# ADC_Shield.net
KiCad netlist of a schematic drawn in Altium Designer
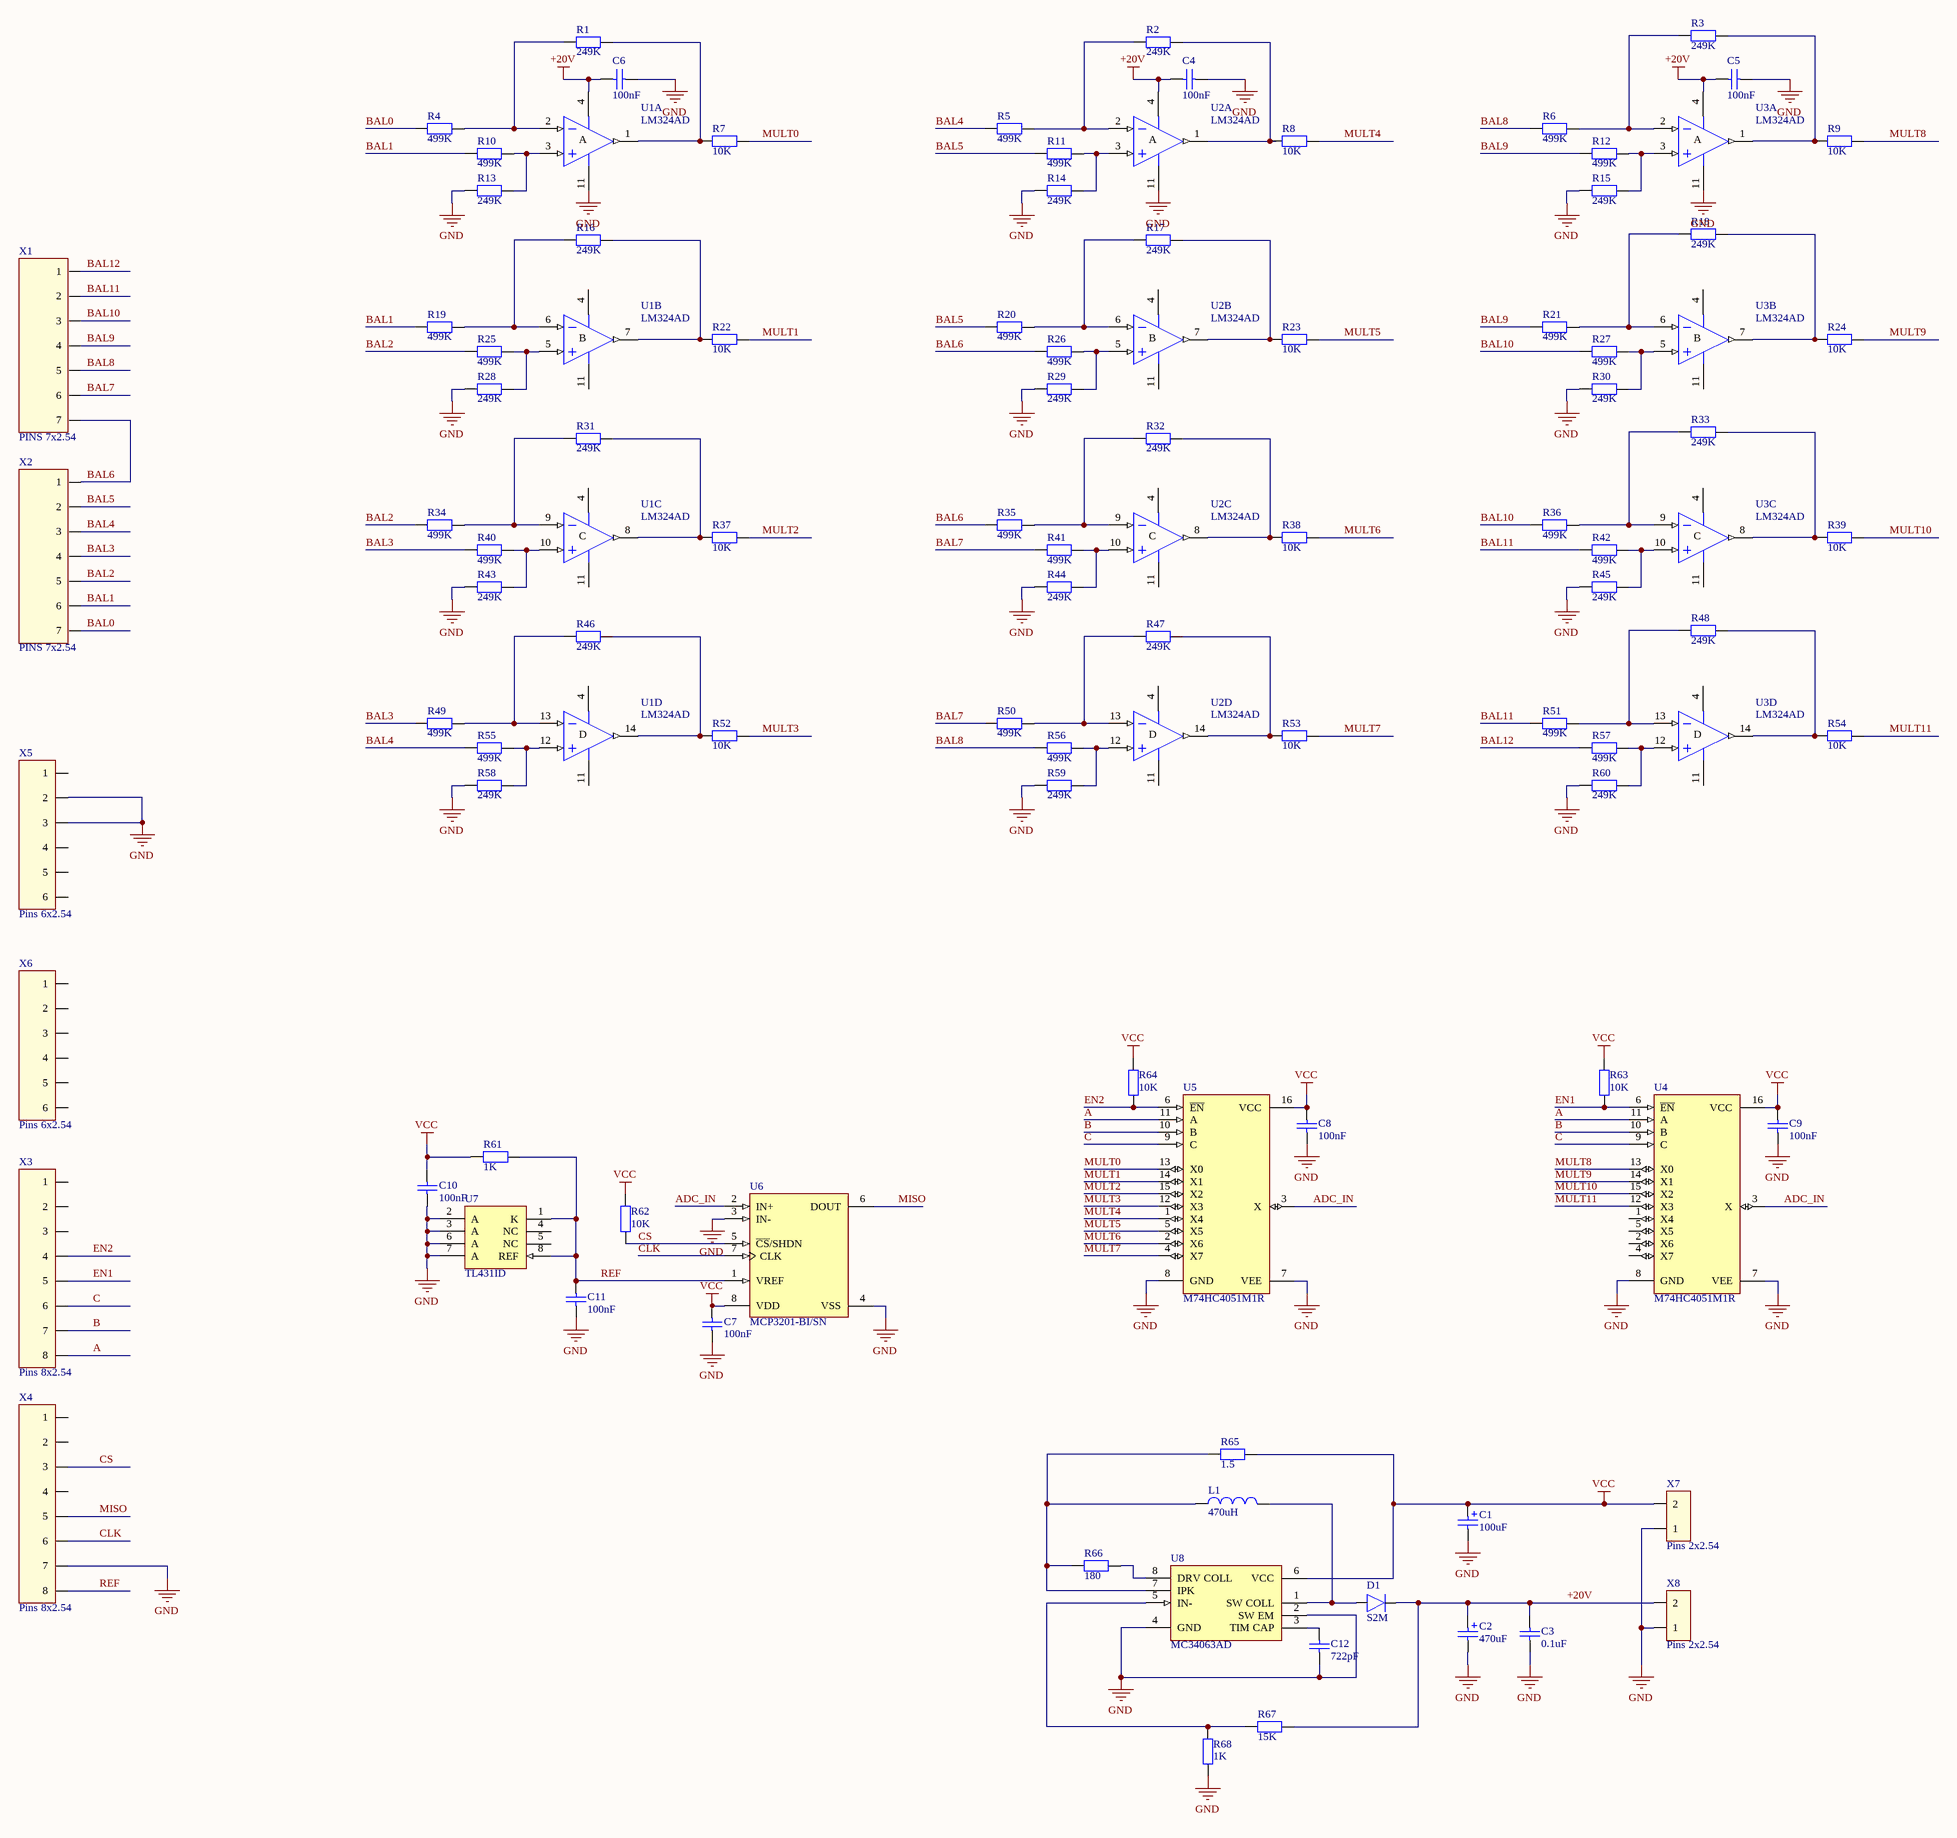
[diagram p0: ADC_Shield.SchDoc]

(export (version "E")
  (design (tool "Eeschema 10.0.6"))
  (components
    (comp (ref "C1")
      (value "100uF")
      (footprint "A_H_pcb_lib:CAP_EL_SMD_6.3mm")
      (libsource (lib "A_H_sch_lib") (part "Cond_polar"))
    )
    (comp (ref "C2")
      (value "470uF")
      (footprint "A_H_pcb_lib:Cap_El_SMD_10mm")
      (libsource (lib "A_H_sch_lib") (part "Cond_polar"))
    )
    (comp (ref "C3")
      (value "0.1uF")
      (footprint "A_H_pcb_lib:C0805")
      (libsource (lib "A_H_sch_lib") (part "Condensator"))
    )
    (comp (ref "C4")
      (value "100nF")
      (footprint "A_H_pcb_lib:C0805")
      (libsource (lib "A_H_sch_lib") (part "Condensator"))
    )
    (comp (ref "C5")
      (value "100nF")
      (footprint "A_H_pcb_lib:C0805")
      (libsource (lib "A_H_sch_lib") (part "Condensator"))
    )
    (comp (ref "C6")
      (value "100nF")
      (footprint "A_H_pcb_lib:C0805")
      (libsource (lib "A_H_sch_lib") (part "Condensator"))
    )
    (comp (ref "C7")
      (value "100nF")
      (footprint "A_H_pcb_lib:C0805")
      (libsource (lib "A_H_sch_lib") (part "Condensator"))
    )
    (comp (ref "C8")
      (value "100nF")
      (footprint "A_H_pcb_lib:C0805")
      (libsource (lib "A_H_sch_lib") (part "Condensator"))
    )
    (comp (ref "C9")
      (value "100nF")
      (footprint "A_H_pcb_lib:C0805")
      (libsource (lib "A_H_sch_lib") (part "Condensator"))
    )
    (comp (ref "C10")
      (value "100nF")
      (footprint "A_H_pcb_lib:C0805")
      (libsource (lib "A_H_sch_lib") (part "Condensator"))
    )
    (comp (ref "C11")
      (value "100nF")
      (footprint "A_H_pcb_lib:C0805")
      (libsource (lib "A_H_sch_lib") (part "Condensator"))
    )
    (comp (ref "C12")
      (value "722pF")
      (footprint "A_H_pcb_lib:C0805")
      (libsource (lib "A_H_sch_lib") (part "Condensator"))
    )
    (comp (ref "D1")
      (value "S2M")
      (footprint "A_H_pcb_lib:SMB_DIODE")
      (libsource (lib "A_H_sch_lib") (part "Diod"))
    )
    (comp (ref "L1")
      (value "470uH")
      (footprint "A_H_pcb_lib:L1812")
      (libsource (lib "A_H_sch_lib") (part "Inductance"))
    )
    (comp (ref "R1") (value "249K") (footprint "R0805") (libsource (lib "A_H_sch_lib") (part "Resistor")))
    (comp (ref "R2") (value "249K") (footprint "R0805") (libsource (lib "A_H_sch_lib") (part "Resistor")))
    (comp (ref "R3") (value "249K") (footprint "R0805") (libsource (lib "A_H_sch_lib") (part "Resistor")))
    (comp (ref "R4") (value "499K") (footprint "R0805") (libsource (lib "A_H_sch_lib") (part "Resistor")))
    (comp (ref "R5") (value "499K") (footprint "R0805") (libsource (lib "A_H_sch_lib") (part "Resistor")))
    (comp (ref "R6") (value "499K") (footprint "R0805") (libsource (lib "A_H_sch_lib") (part "Resistor")))
    (comp (ref "R7") (value "10K") (footprint "R0805") (libsource (lib "A_H_sch_lib") (part "Resistor")))
    (comp (ref "R8") (value "10K") (footprint "R0805") (libsource (lib "A_H_sch_lib") (part "Resistor")))
    (comp (ref "R9") (value "10K") (footprint "R0805") (libsource (lib "A_H_sch_lib") (part "Resistor")))
    (comp (ref "R10") (value "499K") (footprint "R0805") (libsource (lib "A_H_sch_lib") (part "Resistor")))
    (comp (ref "R11") (value "499K") (footprint "R0805") (libsource (lib "A_H_sch_lib") (part "Resistor")))
    (comp (ref "R12") (value "499K") (footprint "R0805") (libsource (lib "A_H_sch_lib") (part "Resistor")))
    (comp (ref "R13") (value "249K") (footprint "R0805") (libsource (lib "A_H_sch_lib") (part "Resistor")))
    (comp (ref "R14") (value "249K") (footprint "R0805") (libsource (lib "A_H_sch_lib") (part "Resistor")))
    (comp (ref "R15") (value "249K") (footprint "R0805") (libsource (lib "A_H_sch_lib") (part "Resistor")))
    (comp (ref "R16") (value "249K") (footprint "R0805") (libsource (lib "A_H_sch_lib") (part "Resistor")))
    (comp (ref "R17") (value "249K") (footprint "R0805") (libsource (lib "A_H_sch_lib") (part "Resistor")))
    (comp (ref "R18") (value "249K") (footprint "R0805") (libsource (lib "A_H_sch_lib") (part "Resistor")))
    (comp (ref "R19") (value "499K") (footprint "R0805") (libsource (lib "A_H_sch_lib") (part "Resistor")))
    (comp (ref "R20") (value "499K") (footprint "R0805") (libsource (lib "A_H_sch_lib") (part "Resistor")))
    (comp (ref "R21") (value "499K") (footprint "R0805") (libsource (lib "A_H_sch_lib") (part "Resistor")))
    (comp (ref "R22") (value "10K") (footprint "R0805") (libsource (lib "A_H_sch_lib") (part "Resistor")))
    (comp (ref "R23") (value "10K") (footprint "R0805") (libsource (lib "A_H_sch_lib") (part "Resistor")))
    (comp (ref "R24") (value "10K") (footprint "R0805") (libsource (lib "A_H_sch_lib") (part "Resistor")))
    (comp (ref "R25") (value "499K") (footprint "R0805") (libsource (lib "A_H_sch_lib") (part "Resistor")))
    (comp (ref "R26") (value "499K") (footprint "R0805") (libsource (lib "A_H_sch_lib") (part "Resistor")))
    (comp (ref "R27") (value "499K") (footprint "R0805") (libsource (lib "A_H_sch_lib") (part "Resistor")))
    (comp (ref "R28") (value "249K") (footprint "R0805") (libsource (lib "A_H_sch_lib") (part "Resistor")))
    (comp (ref "R29") (value "249K") (footprint "R0805") (libsource (lib "A_H_sch_lib") (part "Resistor")))
    (comp (ref "R30") (value "249K") (footprint "R0805") (libsource (lib "A_H_sch_lib") (part "Resistor")))
    (comp (ref "R31") (value "249K") (footprint "R0805") (libsource (lib "A_H_sch_lib") (part "Resistor")))
    (comp (ref "R32") (value "249K") (footprint "R0805") (libsource (lib "A_H_sch_lib") (part "Resistor")))
    (comp (ref "R33") (value "249K") (footprint "R0805") (libsource (lib "A_H_sch_lib") (part "Resistor")))
    (comp (ref "R34") (value "499K") (footprint "R0805") (libsource (lib "A_H_sch_lib") (part "Resistor")))
    (comp (ref "R35") (value "499K") (footprint "R0805") (libsource (lib "A_H_sch_lib") (part "Resistor")))
    (comp (ref "R36") (value "499K") (footprint "R0805") (libsource (lib "A_H_sch_lib") (part "Resistor")))
    (comp (ref "R37") (value "10K") (footprint "R0805") (libsource (lib "A_H_sch_lib") (part "Resistor")))
    (comp (ref "R38") (value "10K") (footprint "R0805") (libsource (lib "A_H_sch_lib") (part "Resistor")))
    (comp (ref "R39") (value "10K") (footprint "R0805") (libsource (lib "A_H_sch_lib") (part "Resistor")))
    (comp (ref "R40") (value "499K") (footprint "R0805") (libsource (lib "A_H_sch_lib") (part "Resistor")))
    (comp (ref "R41") (value "499K") (footprint "R0805") (libsource (lib "A_H_sch_lib") (part "Resistor")))
    (comp (ref "R42") (value "499K") (footprint "R0805") (libsource (lib "A_H_sch_lib") (part "Resistor")))
    (comp (ref "R43") (value "249K") (footprint "R0805") (libsource (lib "A_H_sch_lib") (part "Resistor")))
    (comp (ref "R44") (value "249K") (footprint "R0805") (libsource (lib "A_H_sch_lib") (part "Resistor")))
    (comp (ref "R45") (value "249K") (footprint "R0805") (libsource (lib "A_H_sch_lib") (part "Resistor")))
    (comp (ref "R46") (value "249K") (footprint "R0805") (libsource (lib "A_H_sch_lib") (part "Resistor")))
    (comp (ref "R47") (value "249K") (footprint "R0805") (libsource (lib "A_H_sch_lib") (part "Resistor")))
    (comp (ref "R48") (value "249K") (footprint "R0805") (libsource (lib "A_H_sch_lib") (part "Resistor")))
    (comp (ref "R49") (value "499K") (footprint "R0805") (libsource (lib "A_H_sch_lib") (part "Resistor")))
    (comp (ref "R50") (value "499K") (footprint "R0805") (libsource (lib "A_H_sch_lib") (part "Resistor")))
    (comp (ref "R51") (value "499K") (footprint "R0805") (libsource (lib "A_H_sch_lib") (part "Resistor")))
    (comp (ref "R52") (value "10K") (footprint "R0805") (libsource (lib "A_H_sch_lib") (part "Resistor")))
    (comp (ref "R53") (value "10K") (footprint "R0805") (libsource (lib "A_H_sch_lib") (part "Resistor")))
    (comp (ref "R54") (value "10K") (footprint "R0805") (libsource (lib "A_H_sch_lib") (part "Resistor")))
    (comp (ref "R55") (value "499K") (footprint "R0805") (libsource (lib "A_H_sch_lib") (part "Resistor")))
    (comp (ref "R56") (value "499K") (footprint "R0805") (libsource (lib "A_H_sch_lib") (part "Resistor")))
    (comp (ref "R57") (value "499K") (footprint "R0805") (libsource (lib "A_H_sch_lib") (part "Resistor")))
    (comp (ref "R58") (value "249K") (footprint "R0805") (libsource (lib "A_H_sch_lib") (part "Resistor")))
    (comp (ref "R59") (value "249K") (footprint "R0805") (libsource (lib "A_H_sch_lib") (part "Resistor")))
    (comp (ref "R60") (value "249K") (footprint "R0805") (libsource (lib "A_H_sch_lib") (part "Resistor")))
    (comp (ref "R61") (value "1K") (footprint "R0805") (libsource (lib "A_H_sch_lib") (part "Resistor")))
    (comp (ref "R62") (value "10K") (footprint "R0805") (libsource (lib "") (part "Resistor_1")))
    (comp (ref "R63") (value "10K") (footprint "R0805") (libsource (lib "") (part "Resistor_1")))
    (comp (ref "R64") (value "10K") (footprint "R0805") (libsource (lib "") (part "Resistor_1")))
    (comp (ref "R65") (value "1.5") (footprint "R0805") (libsource (lib "") (part "Resistor_2")))
    (comp (ref "R66") (value "180") (footprint "R0805") (libsource (lib "") (part "Resistor_2")))
    (comp (ref "R67") (value "15K") (footprint "R0805") (libsource (lib "A_H_sch_lib") (part "Resistor")))
    (comp (ref "R68") (value "1K") (footprint "R0805") (libsource (lib "") (part "Resistor_1")))
    (comp (ref "U1")
      (value "LM324AD")
      (footprint "SO14_N")
      (description "Low-Power Quad Operational Amplifier")
      (fields (field (name "PUBLISHER") "Altium Limited"))
      (libsource (lib "ST Operational Amplifier") (part "LM324AD"))
    )
    (comp (ref "U2")
      (value "LM324AD")
      (footprint "SO14_N")
      (description "Low-Power Quad Operational Amplifier")
      (fields (field (name "PUBLISHER") "Altium Limited"))
      (libsource (lib "ST Operational Amplifier") (part "LM324AD"))
    )
    (comp (ref "U3")
      (value "LM324AD")
      (footprint "SO14_N")
      (description "Low-Power Quad Operational Amplifier")
      (fields (field (name "PUBLISHER") "Altium Limited"))
      (libsource (lib "ST Operational Amplifier") (part "LM324AD"))
    )
    (comp (ref "U4")
      (value "M74HC4051M1R")
      (footprint "SO16_N")
      (description "Analog Multiplexer/Demultiplexer Single 8-Channel")
      (fields (field (name "PUBLISHER") "Altium Limited"))
      (libsource (lib "ST Logic Multiplexer") (part "M74HC4051M1R"))
    )
    (comp (ref "U5")
      (value "M74HC4051M1R")
      (footprint "SO16_N")
      (description "Analog Multiplexer/Demultiplexer Single 8-Channel")
      (fields (field (name "PUBLISHER") "Altium Limited"))
      (libsource (lib "ST Logic Multiplexer") (part "M74HC4051M1R"))
    )
    (comp (ref "U6")
      (value "MCP3201-BI/SN")
      (footprint "SO8")
      (libsource (lib "A_H_sch_lib") (part "MCP3201-BI/SN"))
    )
    (comp (ref "U7")
      (value "TL431ID")
      (footprint "SO8_N")
      (description "Programmable Voltage Reference")
      (fields (field (name "PUBLISHER") "Altium Limited"))
      (libsource (lib "ST Power Mgt Voltage Reference") (part "TL431ID"))
    )
    (comp (ref "U8")
      (value "MC34063AD")
      (footprint "751-05_N")
      (description "DC-to-DC Converter Control Circuit")
      (fields (field (name "PUBLISHER") "Altium Limited"))
      (libsource (lib "ON Semi Power Mgt DC-DC Converter") (part "MC34063AD"))
    )
    (comp (ref "X1")
      (value "PINS 7x2.54")
      (footprint "A_H_pcb_lib:PINS 7X2.54R angle")
      (libsource (lib "A_H_sch_lib") (part "PINS 7x2.54"))
    )
    (comp (ref "X2")
      (value "PINS 7x2.54")
      (footprint "A_H_pcb_lib:PINS 7X2.54R angle")
      (libsource (lib "A_H_sch_lib") (part "PINS 7x2.54"))
    )
    (comp (ref "X3")
      (value "Pins 8x2.54")
      (footprint "Pins 8x2.54")
      (libsource (lib "A_H_sch_lib") (part "Pins 8x2.54"))
    )
    (comp (ref "X4")
      (value "Pins 8x2.54")
      (footprint "Pins 8x2.54")
      (libsource (lib "A_H_sch_lib") (part "Pins 8x2.54"))
    )
    (comp (ref "X5")
      (value "Pins 6x2.54")
      (footprint "Pins 6x2.54")
      (libsource (lib "A_H_sch_lib") (part "Pins 6x2.54"))
    )
    (comp (ref "X6")
      (value "Pins 6x2.54")
      (footprint "Pins 6x2.54")
      (libsource (lib "A_H_sch_lib") (part "Pins 6x2.54"))
    )
    (comp (ref "X7")
      (value "Pins 2x2.54")
      (footprint "Pins 2x2.54")
      (libsource (lib "A_H_sch_lib") (part "Pins 2x2.54"))
    )
    (comp (ref "X8")
      (value "Pins 2x2.54")
      (footprint "Pins 2x2.54")
      (libsource (lib "A_H_sch_lib") (part "Pins 2x2.54"))
    )
  )
  (nets
    (net (code "1") (name "+20V") (class "Default")
      (node (ref "C2") (pin "1") (pinfunction "1_1") (pintype "passive"))
      (node (ref "C3") (pin "2") (pinfunction "2_2") (pintype "passive"))
      (node (ref "C4") (pin "1") (pinfunction "1_1") (pintype "passive"))
      (node (ref "C5") (pin "1") (pinfunction "1_1") (pintype "passive"))
      (node (ref "C6") (pin "1") (pinfunction "1_1") (pintype "passive"))
      (node (ref "D1") (pin "2") (pinfunction "2_2") (pintype "passive"))
      (node (ref "R67") (pin "2") (pinfunction "2_2") (pintype "passive"))
      (node (ref "U1") (pin "4") (pinfunction "V+_4") (pintype "power_in"))
      (node (ref "U2") (pin "4") (pinfunction "V+_4") (pintype "power_in"))
      (node (ref "U3") (pin "4") (pinfunction "V+_4") (pintype "power_in"))
      (node (ref "X8") (pin "2") (pinfunction "2_2") (pintype "passive"))
    )
    (net (code "2") (name "/A") (class "Default")
      (node (ref "U4") (pin "11") (pinfunction "A_11") (pintype "input"))
      (node (ref "U5") (pin "11") (pinfunction "A_11") (pintype "input"))
      (node (ref "X3") (pin "8") (pinfunction "8_8") (pintype "passive"))
    )
    (net (code "3") (name "/ADC_IN") (class "Default")
      (node (ref "U4") (pin "3") (pinfunction "X_3") (pintype "bidirectional"))
      (node (ref "U5") (pin "3") (pinfunction "X_3") (pintype "bidirectional"))
      (node (ref "U6") (pin "2") (pinfunction "IN+_2") (pintype "input"))
    )
    (net (code "4") (name "/B") (class "Default")
      (node (ref "U4") (pin "10") (pinfunction "B_10") (pintype "input"))
      (node (ref "U5") (pin "10") (pinfunction "B_10") (pintype "input"))
      (node (ref "X3") (pin "7") (pinfunction "7_7") (pintype "passive"))
    )
    (net (code "5") (name "/BAL0") (class "Default")
      (node (ref "R4") (pin "1") (pinfunction "1_1") (pintype "passive"))
      (node (ref "X2") (pin "7") (pinfunction "7_7") (pintype "passive"))
    )
    (net (code "6") (name "/BAL1") (class "Default")
      (node (ref "R10") (pin "1") (pinfunction "1_1") (pintype "passive"))
      (node (ref "R19") (pin "1") (pinfunction "1_1") (pintype "passive"))
      (node (ref "X2") (pin "6") (pinfunction "6_6") (pintype "passive"))
    )
    (net (code "7") (name "/BAL2") (class "Default")
      (node (ref "R25") (pin "1") (pinfunction "1_1") (pintype "passive"))
      (node (ref "R34") (pin "1") (pinfunction "1_1") (pintype "passive"))
      (node (ref "X2") (pin "5") (pinfunction "5_5") (pintype "passive"))
    )
    (net (code "8") (name "/BAL3") (class "Default")
      (node (ref "R40") (pin "1") (pinfunction "1_1") (pintype "passive"))
      (node (ref "R49") (pin "1") (pinfunction "1_1") (pintype "passive"))
      (node (ref "X2") (pin "4") (pinfunction "4_4") (pintype "passive"))
    )
    (net (code "9") (name "/BAL4") (class "Default")
      (node (ref "R5") (pin "1") (pinfunction "1_1") (pintype "passive"))
      (node (ref "R55") (pin "1") (pinfunction "1_1") (pintype "passive"))
      (node (ref "X2") (pin "3") (pinfunction "3_3") (pintype "passive"))
    )
    (net (code "10") (name "/BAL5") (class "Default")
      (node (ref "R11") (pin "1") (pinfunction "1_1") (pintype "passive"))
      (node (ref "R20") (pin "1") (pinfunction "1_1") (pintype "passive"))
      (node (ref "X2") (pin "2") (pinfunction "2_2") (pintype "passive"))
    )
    (net (code "11") (name "/BAL6") (class "Default")
      (node (ref "R26") (pin "1") (pinfunction "1_1") (pintype "passive"))
      (node (ref "R35") (pin "1") (pinfunction "1_1") (pintype "passive"))
      (node (ref "X1") (pin "7") (pinfunction "7_7") (pintype "passive"))
      (node (ref "X2") (pin "1") (pinfunction "1_1") (pintype "passive"))
    )
    (net (code "12") (name "/BAL7") (class "Default")
      (node (ref "R41") (pin "1") (pinfunction "1_1") (pintype "passive"))
      (node (ref "R50") (pin "1") (pinfunction "1_1") (pintype "passive"))
      (node (ref "X1") (pin "6") (pinfunction "6_6") (pintype "passive"))
    )
    (net (code "13") (name "/BAL8") (class "Default")
      (node (ref "R56") (pin "1") (pinfunction "1_1") (pintype "passive"))
      (node (ref "R6") (pin "1") (pinfunction "1_1") (pintype "passive"))
      (node (ref "X1") (pin "5") (pinfunction "5_5") (pintype "passive"))
    )
    (net (code "14") (name "/BAL9") (class "Default")
      (node (ref "R12") (pin "1") (pinfunction "1_1") (pintype "passive"))
      (node (ref "R21") (pin "1") (pinfunction "1_1") (pintype "passive"))
      (node (ref "X1") (pin "4") (pinfunction "4_4") (pintype "passive"))
    )
    (net (code "15") (name "/BAL10") (class "Default")
      (node (ref "R27") (pin "1") (pinfunction "1_1") (pintype "passive"))
      (node (ref "R36") (pin "1") (pinfunction "1_1") (pintype "passive"))
      (node (ref "X1") (pin "3") (pinfunction "3_3") (pintype "passive"))
    )
    (net (code "16") (name "/BAL11") (class "Default")
      (node (ref "R42") (pin "1") (pinfunction "1_1") (pintype "passive"))
      (node (ref "R51") (pin "1") (pinfunction "1_1") (pintype "passive"))
      (node (ref "X1") (pin "2") (pinfunction "2_2") (pintype "passive"))
    )
    (net (code "17") (name "/BAL12") (class "Default")
      (node (ref "R57") (pin "1") (pinfunction "1_1") (pintype "passive"))
      (node (ref "X1") (pin "1") (pinfunction "1_1") (pintype "passive"))
    )
    (net (code "18") (name "/C") (class "Default")
      (node (ref "U4") (pin "9") (pinfunction "C_9") (pintype "input"))
      (node (ref "U5") (pin "9") (pinfunction "C_9") (pintype "input"))
      (node (ref "X3") (pin "6") (pinfunction "6_6") (pintype "passive"))
    )
    (net (code "19") (name "/CLK") (class "Default")
      (node (ref "U6") (pin "7") (pinfunction "CLK_7") (pintype "input"))
      (node (ref "X4") (pin "6") (pinfunction "6_6") (pintype "passive"))
    )
    (net (code "20") (name "/CS") (class "Default")
      (node (ref "R62") (pin "1") (pinfunction "1_1") (pintype "passive"))
      (node (ref "U6") (pin "5") (pinfunction "~{CS}/SHDN_5") (pintype "input"))
      (node (ref "X4") (pin "3") (pinfunction "3_3") (pintype "passive"))
    )
    (net (code "21") (name "/EN1") (class "Default")
      (node (ref "R63") (pin "1") (pinfunction "1_1") (pintype "passive"))
      (node (ref "U4") (pin "6") (pinfunction "~{EN}_6") (pintype "input"))
      (node (ref "X3") (pin "5") (pinfunction "5_5") (pintype "passive"))
    )
    (net (code "22") (name "/EN2") (class "Default")
      (node (ref "R64") (pin "1") (pinfunction "1_1") (pintype "passive"))
      (node (ref "U5") (pin "6") (pinfunction "~{EN}_6") (pintype "input"))
      (node (ref "X3") (pin "4") (pinfunction "4_4") (pintype "passive"))
    )
    (net (code "23") (name "/MISO") (class "Default")
      (node (ref "U6") (pin "6") (pinfunction "DOUT_6") (pintype "tri_state"))
      (node (ref "X4") (pin "5") (pinfunction "5_5") (pintype "passive"))
    )
    (net (code "24") (name "/MULT0") (class "Default")
      (node (ref "R7") (pin "2") (pinfunction "2_2") (pintype "passive"))
      (node (ref "U5") (pin "13") (pinfunction "X0_13") (pintype "bidirectional"))
    )
    (net (code "25") (name "/MULT1") (class "Default")
      (node (ref "R22") (pin "2") (pinfunction "2_2") (pintype "passive"))
      (node (ref "U5") (pin "14") (pinfunction "X1_14") (pintype "bidirectional"))
    )
    (net (code "26") (name "/MULT2") (class "Default")
      (node (ref "R37") (pin "2") (pinfunction "2_2") (pintype "passive"))
      (node (ref "U5") (pin "15") (pinfunction "X2_15") (pintype "bidirectional"))
    )
    (net (code "27") (name "/MULT3") (class "Default")
      (node (ref "R52") (pin "2") (pinfunction "2_2") (pintype "passive"))
      (node (ref "U5") (pin "12") (pinfunction "X3_12") (pintype "bidirectional"))
    )
    (net (code "28") (name "/MULT4") (class "Default")
      (node (ref "R8") (pin "2") (pinfunction "2_2") (pintype "passive"))
      (node (ref "U5") (pin "1") (pinfunction "X4_1") (pintype "bidirectional"))
    )
    (net (code "29") (name "/MULT5") (class "Default")
      (node (ref "R23") (pin "2") (pinfunction "2_2") (pintype "passive"))
      (node (ref "U5") (pin "5") (pinfunction "X5_5") (pintype "bidirectional"))
    )
    (net (code "30") (name "/MULT6") (class "Default")
      (node (ref "R38") (pin "2") (pinfunction "2_2") (pintype "passive"))
      (node (ref "U5") (pin "2") (pinfunction "X6_2") (pintype "bidirectional"))
    )
    (net (code "31") (name "/MULT7") (class "Default")
      (node (ref "R53") (pin "2") (pinfunction "2_2") (pintype "passive"))
      (node (ref "U5") (pin "4") (pinfunction "X7_4") (pintype "bidirectional"))
    )
    (net (code "32") (name "/MULT8") (class "Default")
      (node (ref "R9") (pin "2") (pinfunction "2_2") (pintype "passive"))
      (node (ref "U4") (pin "13") (pinfunction "X0_13") (pintype "bidirectional"))
    )
    (net (code "33") (name "/MULT9") (class "Default")
      (node (ref "R24") (pin "2") (pinfunction "2_2") (pintype "passive"))
      (node (ref "U4") (pin "14") (pinfunction "X1_14") (pintype "bidirectional"))
    )
    (net (code "34") (name "/MULT10") (class "Default")
      (node (ref "R39") (pin "2") (pinfunction "2_2") (pintype "passive"))
      (node (ref "U4") (pin "15") (pinfunction "X2_15") (pintype "bidirectional"))
    )
    (net (code "35") (name "/MULT11") (class "Default")
      (node (ref "R54") (pin "2") (pinfunction "2_2") (pintype "passive"))
      (node (ref "U4") (pin "12") (pinfunction "X3_12") (pintype "bidirectional"))
    )
    (net (code "36") (name "/REF") (class "Default")
      (node (ref "C11") (pin "2") (pinfunction "2_2") (pintype "passive"))
      (node (ref "R61") (pin "2") (pinfunction "2_2") (pintype "passive"))
      (node (ref "U6") (pin "1") (pinfunction "VREF_1") (pintype "input"))
      (node (ref "U7") (pin "1") (pinfunction "K_1") (pintype "passive"))
      (node (ref "U7") (pin "8") (pinfunction "REF_8") (pintype "input"))
      (node (ref "X4") (pin "8") (pinfunction "8_8") (pintype "passive"))
    )
    (net (code "37") (name "GND") (class "Default")
      (node (ref "C1") (pin "2") (pinfunction "2_2") (pintype "passive"))
      (node (ref "C10") (pin "1") (pinfunction "1_1") (pintype "passive"))
      (node (ref "C11") (pin "1") (pinfunction "1_1") (pintype "passive"))
      (node (ref "C12") (pin "1") (pinfunction "1_1") (pintype "passive"))
      (node (ref "C2") (pin "2") (pinfunction "2_2") (pintype "passive"))
      (node (ref "C3") (pin "1") (pinfunction "1_1") (pintype "passive"))
      (node (ref "C4") (pin "2") (pinfunction "2_2") (pintype "passive"))
      (node (ref "C5") (pin "2") (pinfunction "2_2") (pintype "passive"))
      (node (ref "C6") (pin "2") (pinfunction "2_2") (pintype "passive"))
      (node (ref "C7") (pin "1") (pinfunction "1_1") (pintype "passive"))
      (node (ref "C8") (pin "1") (pinfunction "1_1") (pintype "passive"))
      (node (ref "C9") (pin "1") (pinfunction "1_1") (pintype "passive"))
      (node (ref "R13") (pin "1") (pinfunction "1_1") (pintype "passive"))
      (node (ref "R14") (pin "1") (pinfunction "1_1") (pintype "passive"))
      (node (ref "R15") (pin "1") (pinfunction "1_1") (pintype "passive"))
      (node (ref "R28") (pin "1") (pinfunction "1_1") (pintype "passive"))
      (node (ref "R29") (pin "1") (pinfunction "1_1") (pintype "passive"))
      (node (ref "R30") (pin "1") (pinfunction "1_1") (pintype "passive"))
      (node (ref "R43") (pin "1") (pinfunction "1_1") (pintype "passive"))
      (node (ref "R44") (pin "1") (pinfunction "1_1") (pintype "passive"))
      (node (ref "R45") (pin "1") (pinfunction "1_1") (pintype "passive"))
      (node (ref "R58") (pin "1") (pinfunction "1_1") (pintype "passive"))
      (node (ref "R59") (pin "1") (pinfunction "1_1") (pintype "passive"))
      (node (ref "R60") (pin "1") (pinfunction "1_1") (pintype "passive"))
      (node (ref "R68") (pin "1") (pinfunction "1_1") (pintype "passive"))
      (node (ref "U1") (pin "11") (pinfunction "V-_11") (pintype "power_in"))
      (node (ref "U2") (pin "11") (pinfunction "V-_11") (pintype "power_in"))
      (node (ref "U3") (pin "11") (pinfunction "V-_11") (pintype "power_in"))
      (node (ref "U4") (pin "7") (pinfunction "VEE_7") (pintype "power_in"))
      (node (ref "U4") (pin "8") (pinfunction "GND_8") (pintype "power_in"))
      (node (ref "U5") (pin "7") (pinfunction "VEE_7") (pintype "power_in"))
      (node (ref "U5") (pin "8") (pinfunction "GND_8") (pintype "power_in"))
      (node (ref "U6") (pin "3") (pinfunction "IN-_3") (pintype "input"))
      (node (ref "U6") (pin "4") (pinfunction "VSS_4") (pintype "power_in"))
      (node (ref "U7") (pin "2") (pinfunction "A_2") (pintype "passive"))
      (node (ref "U7") (pin "3") (pinfunction "A_3") (pintype "passive"))
      (node (ref "U7") (pin "6") (pinfunction "A_6") (pintype "passive"))
      (node (ref "U7") (pin "7") (pinfunction "A_7") (pintype "passive"))
      (node (ref "U8") (pin "2") (pinfunction "SW_EM_2") (pintype "passive"))
      (node (ref "U8") (pin "4") (pinfunction "GND_4") (pintype "power_in"))
      (node (ref "X4") (pin "7") (pinfunction "7_7") (pintype "passive"))
      (node (ref "X5") (pin "2") (pinfunction "2_2") (pintype "passive"))
      (node (ref "X5") (pin "3") (pinfunction "3_3") (pintype "passive"))
      (node (ref "X7") (pin "1") (pinfunction "1_1") (pintype "passive"))
      (node (ref "X8") (pin "1") (pinfunction "1_1") (pintype "passive"))
    )
    (net (code "38") (name "Net-(U1A-IN+)") (class "Default")
      (node (ref "R10") (pin "2") (pinfunction "2_2") (pintype "passive"))
      (node (ref "R13") (pin "2") (pinfunction "2_2") (pintype "passive"))
      (node (ref "U1") (pin "3") (pinfunction "IN+_3") (pintype "input"))
    )
    (net (code "39") (name "Net-(U1A-IN-)") (class "Default")
      (node (ref "R1") (pin "1") (pinfunction "1_1") (pintype "passive"))
      (node (ref "R4") (pin "2") (pinfunction "2_2") (pintype "passive"))
      (node (ref "U1") (pin "2") (pinfunction "IN-_2") (pintype "input"))
    )
    (net (code "40") (name "Net-(U1A-OUT)") (class "Default")
      (node (ref "R1") (pin "2") (pinfunction "2_2") (pintype "passive"))
      (node (ref "R7") (pin "1") (pinfunction "1_1") (pintype "passive"))
      (node (ref "U1") (pin "1") (pinfunction "OUT_1") (pintype "output"))
    )
    (net (code "41") (name "Net-(U1B-IN+)") (class "Default")
      (node (ref "R25") (pin "2") (pinfunction "2_2") (pintype "passive"))
      (node (ref "R28") (pin "2") (pinfunction "2_2") (pintype "passive"))
      (node (ref "U1") (pin "5") (pinfunction "IN+_5") (pintype "input"))
    )
    (net (code "42") (name "Net-(U1B-IN-)") (class "Default")
      (node (ref "R16") (pin "1") (pinfunction "1_1") (pintype "passive"))
      (node (ref "R19") (pin "2") (pinfunction "2_2") (pintype "passive"))
      (node (ref "U1") (pin "6") (pinfunction "IN-_6") (pintype "input"))
    )
    (net (code "43") (name "Net-(U1B-OUT)") (class "Default")
      (node (ref "R16") (pin "2") (pinfunction "2_2") (pintype "passive"))
      (node (ref "R22") (pin "1") (pinfunction "1_1") (pintype "passive"))
      (node (ref "U1") (pin "7") (pinfunction "OUT_7") (pintype "output"))
    )
    (net (code "44") (name "Net-(U1C-IN+)") (class "Default")
      (node (ref "R40") (pin "2") (pinfunction "2_2") (pintype "passive"))
      (node (ref "R43") (pin "2") (pinfunction "2_2") (pintype "passive"))
      (node (ref "U1") (pin "10") (pinfunction "IN+_10") (pintype "input"))
    )
    (net (code "45") (name "Net-(U1C-IN-)") (class "Default")
      (node (ref "R31") (pin "1") (pinfunction "1_1") (pintype "passive"))
      (node (ref "R34") (pin "2") (pinfunction "2_2") (pintype "passive"))
      (node (ref "U1") (pin "9") (pinfunction "IN-_9") (pintype "input"))
    )
    (net (code "46") (name "Net-(U1C-OUT)") (class "Default")
      (node (ref "R31") (pin "2") (pinfunction "2_2") (pintype "passive"))
      (node (ref "R37") (pin "1") (pinfunction "1_1") (pintype "passive"))
      (node (ref "U1") (pin "8") (pinfunction "OUT_8") (pintype "output"))
    )
    (net (code "47") (name "Net-(U1D-IN+)") (class "Default")
      (node (ref "R55") (pin "2") (pinfunction "2_2") (pintype "passive"))
      (node (ref "R58") (pin "2") (pinfunction "2_2") (pintype "passive"))
      (node (ref "U1") (pin "12") (pinfunction "IN+_12") (pintype "input"))
    )
    (net (code "48") (name "Net-(U1D-IN-)") (class "Default")
      (node (ref "R46") (pin "1") (pinfunction "1_1") (pintype "passive"))
      (node (ref "R49") (pin "2") (pinfunction "2_2") (pintype "passive"))
      (node (ref "U1") (pin "13") (pinfunction "IN-_13") (pintype "input"))
    )
    (net (code "49") (name "Net-(U1D-OUT)") (class "Default")
      (node (ref "R46") (pin "2") (pinfunction "2_2") (pintype "passive"))
      (node (ref "R52") (pin "1") (pinfunction "1_1") (pintype "passive"))
      (node (ref "U1") (pin "14") (pinfunction "OUT_14") (pintype "output"))
    )
    (net (code "50") (name "Net-(U2A-IN+)") (class "Default")
      (node (ref "R11") (pin "2") (pinfunction "2_2") (pintype "passive"))
      (node (ref "R14") (pin "2") (pinfunction "2_2") (pintype "passive"))
      (node (ref "U2") (pin "3") (pinfunction "IN+_3") (pintype "input"))
    )
    (net (code "51") (name "Net-(U2A-IN-)") (class "Default")
      (node (ref "R2") (pin "1") (pinfunction "1_1") (pintype "passive"))
      (node (ref "R5") (pin "2") (pinfunction "2_2") (pintype "passive"))
      (node (ref "U2") (pin "2") (pinfunction "IN-_2") (pintype "input"))
    )
    (net (code "52") (name "Net-(U2A-OUT)") (class "Default")
      (node (ref "R2") (pin "2") (pinfunction "2_2") (pintype "passive"))
      (node (ref "R8") (pin "1") (pinfunction "1_1") (pintype "passive"))
      (node (ref "U2") (pin "1") (pinfunction "OUT_1") (pintype "output"))
    )
    (net (code "53") (name "Net-(U2B-IN+)") (class "Default")
      (node (ref "R26") (pin "2") (pinfunction "2_2") (pintype "passive"))
      (node (ref "R29") (pin "2") (pinfunction "2_2") (pintype "passive"))
      (node (ref "U2") (pin "5") (pinfunction "IN+_5") (pintype "input"))
    )
    (net (code "54") (name "Net-(U2B-IN-)") (class "Default")
      (node (ref "R17") (pin "1") (pinfunction "1_1") (pintype "passive"))
      (node (ref "R20") (pin "2") (pinfunction "2_2") (pintype "passive"))
      (node (ref "U2") (pin "6") (pinfunction "IN-_6") (pintype "input"))
    )
    (net (code "55") (name "Net-(U2B-OUT)") (class "Default")
      (node (ref "R17") (pin "2") (pinfunction "2_2") (pintype "passive"))
      (node (ref "R23") (pin "1") (pinfunction "1_1") (pintype "passive"))
      (node (ref "U2") (pin "7") (pinfunction "OUT_7") (pintype "output"))
    )
    (net (code "56") (name "Net-(U2C-IN+)") (class "Default")
      (node (ref "R41") (pin "2") (pinfunction "2_2") (pintype "passive"))
      (node (ref "R44") (pin "2") (pinfunction "2_2") (pintype "passive"))
      (node (ref "U2") (pin "10") (pinfunction "IN+_10") (pintype "input"))
    )
    (net (code "57") (name "Net-(U2C-IN-)") (class "Default")
      (node (ref "R32") (pin "1") (pinfunction "1_1") (pintype "passive"))
      (node (ref "R35") (pin "2") (pinfunction "2_2") (pintype "passive"))
      (node (ref "U2") (pin "9") (pinfunction "IN-_9") (pintype "input"))
    )
    (net (code "58") (name "Net-(U2C-OUT)") (class "Default")
      (node (ref "R32") (pin "2") (pinfunction "2_2") (pintype "passive"))
      (node (ref "R38") (pin "1") (pinfunction "1_1") (pintype "passive"))
      (node (ref "U2") (pin "8") (pinfunction "OUT_8") (pintype "output"))
    )
    (net (code "59") (name "Net-(U2D-IN+)") (class "Default")
      (node (ref "R56") (pin "2") (pinfunction "2_2") (pintype "passive"))
      (node (ref "R59") (pin "2") (pinfunction "2_2") (pintype "passive"))
      (node (ref "U2") (pin "12") (pinfunction "IN+_12") (pintype "input"))
    )
    (net (code "60") (name "Net-(U2D-IN-)") (class "Default")
      (node (ref "R47") (pin "1") (pinfunction "1_1") (pintype "passive"))
      (node (ref "R50") (pin "2") (pinfunction "2_2") (pintype "passive"))
      (node (ref "U2") (pin "13") (pinfunction "IN-_13") (pintype "input"))
    )
    (net (code "61") (name "Net-(U2D-OUT)") (class "Default")
      (node (ref "R47") (pin "2") (pinfunction "2_2") (pintype "passive"))
      (node (ref "R53") (pin "1") (pinfunction "1_1") (pintype "passive"))
      (node (ref "U2") (pin "14") (pinfunction "OUT_14") (pintype "output"))
    )
    (net (code "62") (name "Net-(U3A-IN+)") (class "Default")
      (node (ref "R12") (pin "2") (pinfunction "2_2") (pintype "passive"))
      (node (ref "R15") (pin "2") (pinfunction "2_2") (pintype "passive"))
      (node (ref "U3") (pin "3") (pinfunction "IN+_3") (pintype "input"))
    )
    (net (code "63") (name "Net-(U3A-IN-)") (class "Default")
      (node (ref "R3") (pin "1") (pinfunction "1_1") (pintype "passive"))
      (node (ref "R6") (pin "2") (pinfunction "2_2") (pintype "passive"))
      (node (ref "U3") (pin "2") (pinfunction "IN-_2") (pintype "input"))
    )
    (net (code "64") (name "Net-(U3A-OUT)") (class "Default")
      (node (ref "R3") (pin "2") (pinfunction "2_2") (pintype "passive"))
      (node (ref "R9") (pin "1") (pinfunction "1_1") (pintype "passive"))
      (node (ref "U3") (pin "1") (pinfunction "OUT_1") (pintype "output"))
    )
    (net (code "65") (name "Net-(U3B-IN+)") (class "Default")
      (node (ref "R27") (pin "2") (pinfunction "2_2") (pintype "passive"))
      (node (ref "R30") (pin "2") (pinfunction "2_2") (pintype "passive"))
      (node (ref "U3") (pin "5") (pinfunction "IN+_5") (pintype "input"))
    )
    (net (code "66") (name "Net-(U3B-IN-)") (class "Default")
      (node (ref "R18") (pin "1") (pinfunction "1_1") (pintype "passive"))
      (node (ref "R21") (pin "2") (pinfunction "2_2") (pintype "passive"))
      (node (ref "U3") (pin "6") (pinfunction "IN-_6") (pintype "input"))
    )
    (net (code "67") (name "Net-(U3B-OUT)") (class "Default")
      (node (ref "R18") (pin "2") (pinfunction "2_2") (pintype "passive"))
      (node (ref "R24") (pin "1") (pinfunction "1_1") (pintype "passive"))
      (node (ref "U3") (pin "7") (pinfunction "OUT_7") (pintype "output"))
    )
    (net (code "68") (name "Net-(U3C-IN+)") (class "Default")
      (node (ref "R42") (pin "2") (pinfunction "2_2") (pintype "passive"))
      (node (ref "R45") (pin "2") (pinfunction "2_2") (pintype "passive"))
      (node (ref "U3") (pin "10") (pinfunction "IN+_10") (pintype "input"))
    )
    (net (code "69") (name "Net-(U3C-IN-)") (class "Default")
      (node (ref "R33") (pin "1") (pinfunction "1_1") (pintype "passive"))
      (node (ref "R36") (pin "2") (pinfunction "2_2") (pintype "passive"))
      (node (ref "U3") (pin "9") (pinfunction "IN-_9") (pintype "input"))
    )
    (net (code "70") (name "Net-(U3C-OUT)") (class "Default")
      (node (ref "R33") (pin "2") (pinfunction "2_2") (pintype "passive"))
      (node (ref "R39") (pin "1") (pinfunction "1_1") (pintype "passive"))
      (node (ref "U3") (pin "8") (pinfunction "OUT_8") (pintype "output"))
    )
    (net (code "71") (name "Net-(U3D-IN+)") (class "Default")
      (node (ref "R57") (pin "2") (pinfunction "2_2") (pintype "passive"))
      (node (ref "R60") (pin "2") (pinfunction "2_2") (pintype "passive"))
      (node (ref "U3") (pin "12") (pinfunction "IN+_12") (pintype "input"))
    )
    (net (code "72") (name "Net-(U3D-IN-)") (class "Default")
      (node (ref "R48") (pin "1") (pinfunction "1_1") (pintype "passive"))
      (node (ref "R51") (pin "2") (pinfunction "2_2") (pintype "passive"))
      (node (ref "U3") (pin "13") (pinfunction "IN-_13") (pintype "input"))
    )
    (net (code "73") (name "Net-(U3D-OUT)") (class "Default")
      (node (ref "R48") (pin "2") (pinfunction "2_2") (pintype "passive"))
      (node (ref "R54") (pin "1") (pinfunction "1_1") (pintype "passive"))
      (node (ref "U3") (pin "14") (pinfunction "OUT_14") (pintype "output"))
    )
    (net (code "74") (name "Net-(U8-DRV_COLL)") (class "Default")
      (node (ref "R66") (pin "1") (pinfunction "1_1") (pintype "passive"))
      (node (ref "U8") (pin "8") (pinfunction "DRV_COLL_8") (pintype "open_collector"))
    )
    (net (code "75") (name "Net-(U8-IN-)") (class "Default")
      (node (ref "R67") (pin "1") (pinfunction "1_1") (pintype "passive"))
      (node (ref "R68") (pin "2") (pinfunction "2_2") (pintype "passive"))
      (node (ref "U8") (pin "5") (pinfunction "IN-_5") (pintype "input"))
    )
    (net (code "76") (name "Net-(U8-IPK)") (class "Default")
      (node (ref "L1") (pin "1") (pinfunction "1_1") (pintype "passive"))
      (node (ref "R65") (pin "2") (pinfunction "2_2") (pintype "passive"))
      (node (ref "R66") (pin "2") (pinfunction "2_2") (pintype "passive"))
      (node (ref "U8") (pin "7") (pinfunction "IPK_7") (pintype "passive"))
    )
    (net (code "77") (name "Net-(U8-SW_COLL)") (class "Default")
      (node (ref "D1") (pin "1") (pinfunction "1_1") (pintype "passive"))
      (node (ref "L1") (pin "2") (pinfunction "2_2") (pintype "passive"))
      (node (ref "U8") (pin "1") (pinfunction "SW_COLL_1") (pintype "passive"))
    )
    (net (code "78") (name "Net-(U8-TIM_CAP)") (class "Default")
      (node (ref "C12") (pin "2") (pinfunction "2_2") (pintype "passive"))
      (node (ref "U8") (pin "3") (pinfunction "TIM_CAP_3") (pintype "passive"))
    )
    (net (code "79") (name "VCC") (class "Default")
      (node (ref "C1") (pin "1") (pinfunction "1_1") (pintype "passive"))
      (node (ref "C10") (pin "2") (pinfunction "2_2") (pintype "passive"))
      (node (ref "C7") (pin "2") (pinfunction "2_2") (pintype "passive"))
      (node (ref "C8") (pin "2") (pinfunction "2_2") (pintype "passive"))
      (node (ref "C9") (pin "2") (pinfunction "2_2") (pintype "passive"))
      (node (ref "R61") (pin "1") (pinfunction "1_1") (pintype "passive"))
      (node (ref "R62") (pin "2") (pinfunction "2_2") (pintype "passive"))
      (node (ref "R63") (pin "2") (pinfunction "2_2") (pintype "passive"))
      (node (ref "R64") (pin "2") (pinfunction "2_2") (pintype "passive"))
      (node (ref "R65") (pin "1") (pinfunction "1_1") (pintype "passive"))
      (node (ref "U4") (pin "16") (pinfunction "VCC_16") (pintype "power_in"))
      (node (ref "U5") (pin "16") (pinfunction "VCC_16") (pintype "power_in"))
      (node (ref "U6") (pin "8") (pinfunction "VDD_8") (pintype "power_in"))
      (node (ref "U8") (pin "6") (pinfunction "VCC_6") (pintype "power_in"))
      (node (ref "X7") (pin "2") (pinfunction "2_2") (pintype "passive"))
    )
    (net (code "80") (name "unconnected-(U1B-V+-Pad4)") (class "Default")
      (node (ref "U1") (pin "4") (pinfunction "V+_4") (pintype "power_in"))
    )
    (net (code "81") (name "unconnected-(U1B-V--Pad11)") (class "Default")
      (node (ref "U1") (pin "11") (pinfunction "V-_11") (pintype "power_in"))
    )
    (net (code "82") (name "unconnected-(U1C-V+-Pad4)") (class "Default")
      (node (ref "U1") (pin "4") (pinfunction "V+_4") (pintype "power_in"))
    )
    (net (code "83") (name "unconnected-(U1C-V--Pad11)") (class "Default")
      (node (ref "U1") (pin "11") (pinfunction "V-_11") (pintype "power_in"))
    )
    (net (code "84") (name "unconnected-(U1D-V+-Pad4)") (class "Default")
      (node (ref "U1") (pin "4") (pinfunction "V+_4") (pintype "power_in"))
    )
    (net (code "85") (name "unconnected-(U1D-V--Pad11)") (class "Default")
      (node (ref "U1") (pin "11") (pinfunction "V-_11") (pintype "power_in"))
    )
    (net (code "86") (name "unconnected-(U2B-V+-Pad4)") (class "Default")
      (node (ref "U2") (pin "4") (pinfunction "V+_4") (pintype "power_in"))
    )
    (net (code "87") (name "unconnected-(U2B-V--Pad11)") (class "Default")
      (node (ref "U2") (pin "11") (pinfunction "V-_11") (pintype "power_in"))
    )
    (net (code "88") (name "unconnected-(U2C-V+-Pad4)") (class "Default")
      (node (ref "U2") (pin "4") (pinfunction "V+_4") (pintype "power_in"))
    )
    (net (code "89") (name "unconnected-(U2C-V--Pad11)") (class "Default")
      (node (ref "U2") (pin "11") (pinfunction "V-_11") (pintype "power_in"))
    )
    (net (code "90") (name "unconnected-(U2D-V+-Pad4)") (class "Default")
      (node (ref "U2") (pin "4") (pinfunction "V+_4") (pintype "power_in"))
    )
    (net (code "91") (name "unconnected-(U2D-V--Pad11)") (class "Default")
      (node (ref "U2") (pin "11") (pinfunction "V-_11") (pintype "power_in"))
    )
    (net (code "92") (name "unconnected-(U3B-V+-Pad4)") (class "Default")
      (node (ref "U3") (pin "4") (pinfunction "V+_4") (pintype "power_in"))
    )
    (net (code "93") (name "unconnected-(U3B-V--Pad11)") (class "Default")
      (node (ref "U3") (pin "11") (pinfunction "V-_11") (pintype "power_in"))
    )
    (net (code "94") (name "unconnected-(U3C-V+-Pad4)") (class "Default")
      (node (ref "U3") (pin "4") (pinfunction "V+_4") (pintype "power_in"))
    )
    (net (code "95") (name "unconnected-(U3C-V--Pad11)") (class "Default")
      (node (ref "U3") (pin "11") (pinfunction "V-_11") (pintype "power_in"))
    )
    (net (code "96") (name "unconnected-(U3D-V+-Pad4)") (class "Default")
      (node (ref "U3") (pin "4") (pinfunction "V+_4") (pintype "power_in"))
    )
    (net (code "97") (name "unconnected-(U3D-V--Pad11)") (class "Default")
      (node (ref "U3") (pin "11") (pinfunction "V-_11") (pintype "power_in"))
    )
    (net (code "98") (name "unconnected-(U4-X4-Pad1)") (class "Default")
      (node (ref "U4") (pin "1") (pinfunction "X4_1") (pintype "bidirectional"))
    )
    (net (code "99") (name "unconnected-(U4-X5-Pad5)") (class "Default")
      (node (ref "U4") (pin "5") (pinfunction "X5_5") (pintype "bidirectional"))
    )
    (net (code "100") (name "unconnected-(U4-X6-Pad2)") (class "Default")
      (node (ref "U4") (pin "2") (pinfunction "X6_2") (pintype "bidirectional"))
    )
    (net (code "101") (name "unconnected-(U4-X7-Pad4)") (class "Default")
      (node (ref "U4") (pin "4") (pinfunction "X7_4") (pintype "bidirectional"))
    )
    (net (code "102") (name "unconnected-(U7-NC-Pad4)") (class "Default")
      (node (ref "U7") (pin "4") (pinfunction "NC_4") (pintype "passive"))
    )
    (net (code "103") (name "unconnected-(U7-NC-Pad5)") (class "Default")
      (node (ref "U7") (pin "5") (pinfunction "NC_5") (pintype "passive"))
    )
    (net (code "104") (name "unconnected-(X3-Pad1)") (class "Default")
      (node (ref "X3") (pin "1") (pinfunction "1_1") (pintype "passive"))
    )
    (net (code "105") (name "unconnected-(X3-Pad2)") (class "Default")
      (node (ref "X3") (pin "2") (pinfunction "2_2") (pintype "passive"))
    )
    (net (code "106") (name "unconnected-(X3-Pad3)") (class "Default")
      (node (ref "X3") (pin "3") (pinfunction "3_3") (pintype "passive"))
    )
    (net (code "107") (name "unconnected-(X4-Pad1)") (class "Default")
      (node (ref "X4") (pin "1") (pinfunction "1_1") (pintype "passive"))
    )
    (net (code "108") (name "unconnected-(X4-Pad2)") (class "Default")
      (node (ref "X4") (pin "2") (pinfunction "2_2") (pintype "passive"))
    )
    (net (code "109") (name "unconnected-(X4-Pad4)") (class "Default")
      (node (ref "X4") (pin "4") (pinfunction "4_4") (pintype "passive"))
    )
    (net (code "110") (name "unconnected-(X5-Pad1)") (class "Default")
      (node (ref "X5") (pin "1") (pinfunction "1_1") (pintype "passive"))
    )
    (net (code "111") (name "unconnected-(X5-Pad4)") (class "Default")
      (node (ref "X5") (pin "4") (pinfunction "4_4") (pintype "passive"))
    )
    (net (code "112") (name "unconnected-(X5-Pad5)") (class "Default")
      (node (ref "X5") (pin "5") (pinfunction "5_5") (pintype "passive"))
    )
    (net (code "113") (name "unconnected-(X5-Pad6)") (class "Default")
      (node (ref "X5") (pin "6") (pinfunction "6_6") (pintype "passive"))
    )
    (net (code "114") (name "unconnected-(X6-Pad1)") (class "Default")
      (node (ref "X6") (pin "1") (pinfunction "1_1") (pintype "passive"))
    )
    (net (code "115") (name "unconnected-(X6-Pad2)") (class "Default")
      (node (ref "X6") (pin "2") (pinfunction "2_2") (pintype "passive"))
    )
    (net (code "116") (name "unconnected-(X6-Pad3)") (class "Default")
      (node (ref "X6") (pin "3") (pinfunction "3_3") (pintype "passive"))
    )
    (net (code "117") (name "unconnected-(X6-Pad4)") (class "Default")
      (node (ref "X6") (pin "4") (pinfunction "4_4") (pintype "passive"))
    )
    (net (code "118") (name "unconnected-(X6-Pad5)") (class "Default")
      (node (ref "X6") (pin "5") (pinfunction "5_5") (pintype "passive"))
    )
    (net (code "119") (name "unconnected-(X6-Pad6)") (class "Default")
      (node (ref "X6") (pin "6") (pinfunction "6_6") (pintype "passive"))
    )
  )
)
